# Sheet1.net
KiCad netlist of a schematic drawn in Altium Designer
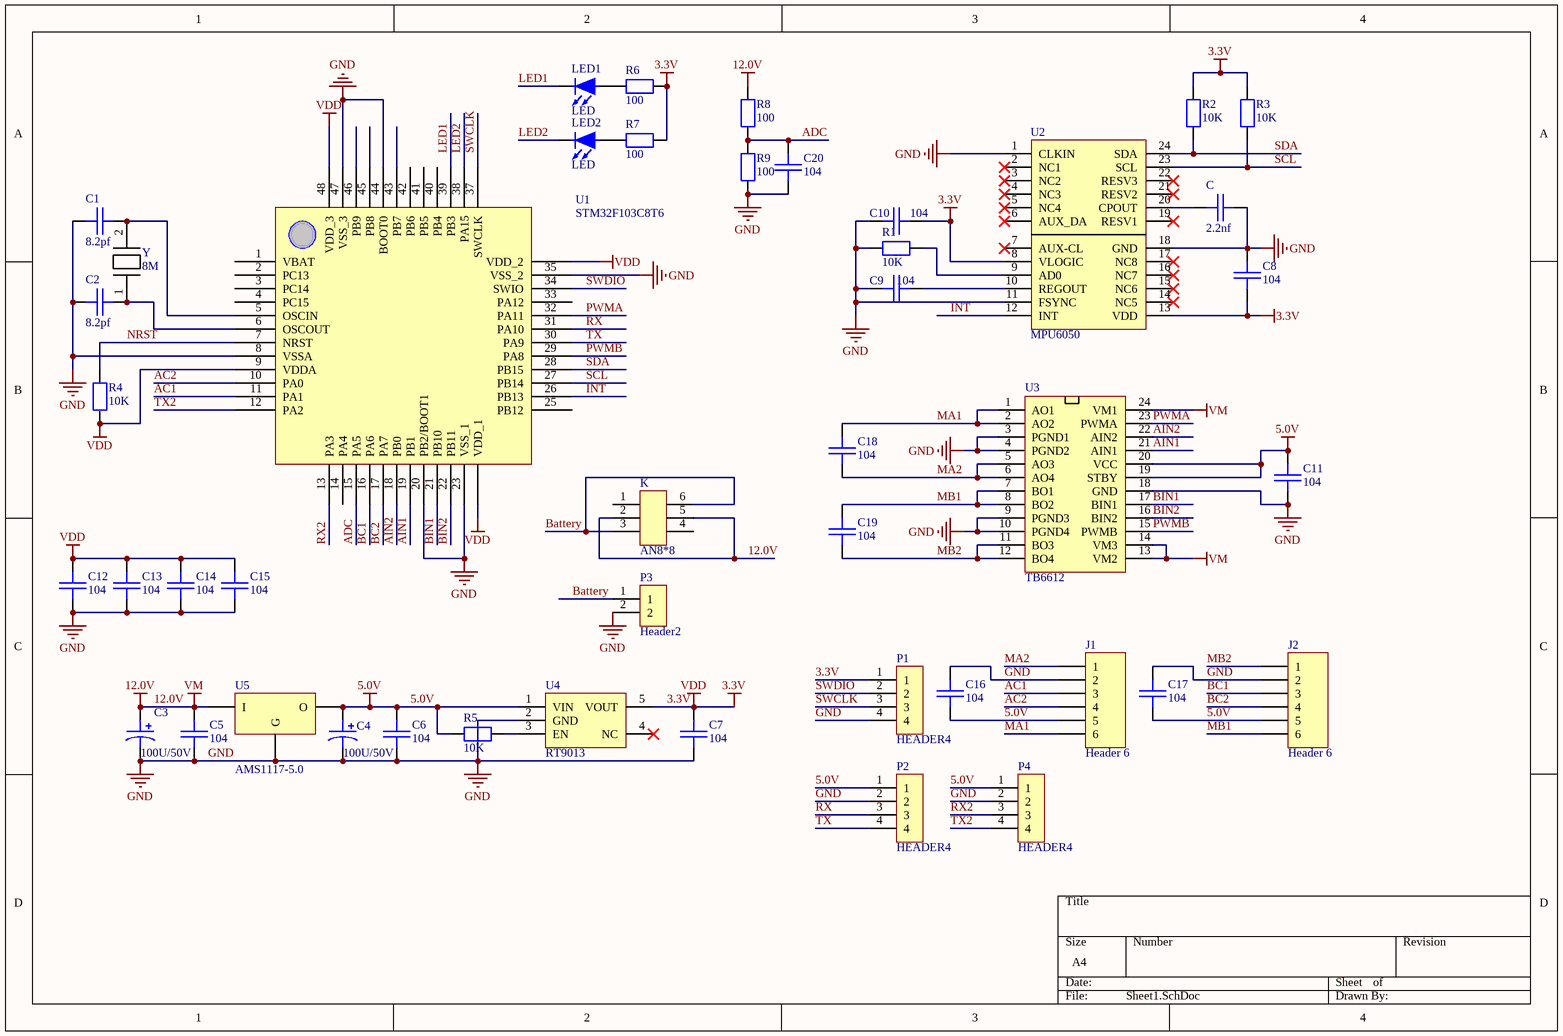
[diagram p0: Sheet1.SchDoc]

(export (version "E")
  (design (tool "Eeschema 10.0.6"))
  (components
    (comp (ref "C") (value "2.2nf") (footprint "0603") (libsource (lib "电容") (part "2.2nf")))
    (comp (ref "C1") (value "8.2pf") (footprint "0805-C") (libsource (lib "电容") (part "8.2pf")))
    (comp (ref "C2") (value "8.2pf") (footprint "0805-C") (libsource (lib "电容") (part "8.2pf")))
    (comp (ref "C3") (value "100U/50V") (footprint "RB_D8_d3.5") (libsource (lib "电容") (part "100U/50V")))
    (comp (ref "C4") (value "100U/50V") (footprint "RB_D8_d3.5") (libsource (lib "电容") (part "100U/50V")))
    (comp (ref "C5") (value "104") (footprint "0805-C") (libsource (lib "电容") (part "8.2pf")))
    (comp (ref "C6") (value "104") (footprint "0805-C") (libsource (lib "电容") (part "8.2pf")))
    (comp (ref "C7") (value "104") (footprint "0805-C") (libsource (lib "电容") (part "8.2pf")))
    (comp (ref "C8") (value "104") (footprint "0805-C") (libsource (lib "电容") (part "8.2pf")))
    (comp (ref "C9") (value "104") (footprint "0805-C") (libsource (lib "电容") (part "8.2pf")))
    (comp (ref "C10") (value "104") (footprint "0805-C") (libsource (lib "电容") (part "8.2pf")))
    (comp (ref "C11") (value "104") (footprint "0805-C") (libsource (lib "电容") (part "8.2pf")))
    (comp (ref "C12") (value "104") (footprint "0805-C") (libsource (lib "电容") (part "8.2pf")))
    (comp (ref "C13") (value "104") (footprint "0805-C") (libsource (lib "电容") (part "8.2pf")))
    (comp (ref "C14") (value "104") (footprint "0805-C") (libsource (lib "电容") (part "8.2pf")))
    (comp (ref "C15") (value "104") (footprint "0805-C") (libsource (lib "电容") (part "8.2pf")))
    (comp (ref "C16") (value "104") (footprint "0805-C") (libsource (lib "电容") (part "8.2pf")))
    (comp (ref "C17") (value "104") (footprint "0805-C") (libsource (lib "电容") (part "8.2pf")))
    (comp (ref "C18") (value "104") (footprint "0805-C") (libsource (lib "电容") (part "8.2pf")))
    (comp (ref "C19") (value "104") (footprint "0805-C") (libsource (lib "电容") (part "8.2pf")))
    (comp (ref "C20") (value "104") (footprint "0805-C") (libsource (lib "电容") (part "8.2pf")))
    (comp (ref "J1")
      (value "Header 6")
      (footprint "HDR1X6")
      (description "Header, 6-Pin")
      (fields (field (name "PUBLISHER") "Altium Limited"))
      (libsource (lib "接插件") (part "Header 6"))
    )
    (comp (ref "J2")
      (value "Header 6")
      (footprint "HDR1X6")
      (description "Header, 6-Pin")
      (fields (field (name "PUBLISHER") "Altium Limited"))
      (libsource (lib "接插件") (part "Header 6"))
    )
    (comp (ref "K") (value "AN8*8") (footprint "DIP-AN88") (libsource (lib "接插件") (part "AN8*8")))
    (comp (ref "LED1") (value "LED") (footprint "LED-0805") (libsource (lib "晶体管") (part "LED")))
    (comp (ref "LED2") (value "LED") (footprint "LED-0805") (libsource (lib "晶体管") (part "LED")))
    (comp (ref "P1") (value "HEADER4") (footprint "HDR1X4") (libsource (lib "接插件") (part "HEADER4")))
    (comp (ref "P2") (value "HEADER4") (footprint "HDR1X4") (libsource (lib "接插件") (part "HEADER4")))
    (comp (ref "P3") (value "Header2") (footprint "HDR1X2") (libsource (lib "接插件") (part "Header2")))
    (comp (ref "P4") (value "HEADER4") (footprint "HDR1X4") (libsource (lib "接插件") (part "HEADER4")))
    (comp (ref "R1") (value "10K") (footprint "0805-R") (libsource (lib "电阻") (part "10K-0805")))
    (comp (ref "R2") (value "10K") (footprint "0805-R") (libsource (lib "电阻") (part "10K-0805")))
    (comp (ref "R3") (value "10K") (footprint "0805-R") (libsource (lib "电阻") (part "10K-0805")))
    (comp (ref "R4") (value "10K") (footprint "0805-R") (libsource (lib "电阻") (part "10K-0805")))
    (comp (ref "R5") (value "10K") (footprint "0805-R") (libsource (lib "电阻") (part "10K-0805")))
    (comp (ref "R6") (value "100") (footprint "0805-R") (libsource (lib "电阻") (part "10K-0805")))
    (comp (ref "R7") (value "100") (footprint "0805-R") (libsource (lib "电阻") (part "10K-0805")))
    (comp (ref "R8") (value "100") (footprint "0805-R") (libsource (lib "电阻") (part "10K-0805")))
    (comp (ref "R9") (value "100") (footprint "0805-R") (libsource (lib "电阻") (part "10K-0805")))
    (comp (ref "U1")
      (value "STM32F103C8T6")
      (footprint "LQFP-48")
      (libsource (lib "IC") (part "STM32F103C8T6"))
    )
    (comp (ref "U2") (value "MPU6050") (footprint "QFN-24") (libsource (lib "IC") (part "MPU6050")))
    (comp (ref "U3") (value "TB6612") (footprint "SSOP-24") (libsource (lib "IC") (part "TB6612")))
    (comp (ref "U4") (value "RT9013") (footprint "SOT-23-5") (libsource (lib "IC") (part "RT9013")))
    (comp (ref "U5") (value "AMS1117-5.0") (footprint "SOT-223") (libsource (lib "IC") (part "AMS1117-5.0")))
    (comp (ref "Y") (value "8M") (footprint "HC-49SMD") (libsource (lib "接插件") (part "晶振 8M")))
  )
  (nets
    (net (code "1") (name "/AC1") (class "Default")
      (node (ref "J1") (pin "3") (pinfunction "3_3") (pintype "passive"))
      (node (ref "U1") (pin "11") (pinfunction "PA1_11") (pintype "passive"))
    )
    (net (code "2") (name "/AC2") (class "Default")
      (node (ref "J1") (pin "4") (pinfunction "4_4") (pintype "passive"))
      (node (ref "U1") (pin "10") (pinfunction "PA0_10") (pintype "passive"))
    )
    (net (code "3") (name "/ADC") (class "Default")
      (node (ref "C20") (pin "1") (pinfunction "1_1") (pintype "passive"))
      (node (ref "R8") (pin "1") (pinfunction "1_1") (pintype "passive"))
      (node (ref "R9") (pin "2") (pinfunction "2_2") (pintype "passive"))
      (node (ref "U1") (pin "15") (pinfunction "PA5_15") (pintype "passive"))
    )
    (net (code "4") (name "/AIN1") (class "Default")
      (node (ref "U1") (pin "19") (pinfunction "PB1_19") (pintype "passive"))
      (node (ref "U3") (pin "21") (pinfunction "AIN1_21") (pintype "passive"))
    )
    (net (code "5") (name "/AIN2") (class "Default")
      (node (ref "U1") (pin "18") (pinfunction "PB0_18") (pintype "passive"))
      (node (ref "U3") (pin "22") (pinfunction "AIN2_22") (pintype "passive"))
    )
    (net (code "6") (name "/BC1") (class "Default")
      (node (ref "J2") (pin "3") (pinfunction "3_3") (pintype "passive"))
      (node (ref "U1") (pin "16") (pinfunction "PA6_16") (pintype "passive"))
    )
    (net (code "7") (name "/BC2") (class "Default")
      (node (ref "J2") (pin "4") (pinfunction "4_4") (pintype "passive"))
      (node (ref "U1") (pin "17") (pinfunction "PA7_17") (pintype "passive"))
    )
    (net (code "8") (name "/BIN1") (class "Default")
      (node (ref "U1") (pin "21") (pinfunction "PB10_21") (pintype "passive"))
      (node (ref "U3") (pin "17") (pinfunction "BIN1_17") (pintype "passive"))
    )
    (net (code "9") (name "/BIN2") (class "Default")
      (node (ref "U1") (pin "22") (pinfunction "PB11_22") (pintype "passive"))
      (node (ref "U3") (pin "16") (pinfunction "BIN2_16") (pintype "passive"))
    )
    (net (code "10") (name "/Battery") (class "Default")
      (node (ref "K") (pin "3") (pinfunction "3_3") (pintype "passive"))
      (node (ref "K") (pin "6") (pinfunction "6_6") (pintype "passive"))
      (node (ref "P3") (pin "1") (pinfunction "1_1") (pintype "passive"))
    )
    (net (code "11") (name "/INT") (class "Default")
      (node (ref "U1") (pin "26") (pinfunction "PB13_26") (pintype "passive"))
      (node (ref "U2") (pin "12") (pinfunction "INT_12") (pintype "passive"))
    )
    (net (code "12") (name "/LED1") (class "Default")
      (node (ref "LED1") (pin "2") (pinfunction "2_2") (pintype "passive"))
      (node (ref "U1") (pin "39") (pinfunction "PB3_39") (pintype "passive"))
    )
    (net (code "13") (name "/LED2") (class "Default")
      (node (ref "LED2") (pin "2") (pinfunction "2_2") (pintype "passive"))
      (node (ref "U1") (pin "38") (pinfunction "PA15_38") (pintype "passive"))
    )
    (net (code "14") (name "/MA1") (class "Default")
      (node (ref "C18") (pin "1") (pinfunction "1_1") (pintype "passive"))
      (node (ref "J1") (pin "6") (pinfunction "6_6") (pintype "passive"))
      (node (ref "U3") (pin "1") (pinfunction "AO1_1") (pintype "passive"))
      (node (ref "U3") (pin "2") (pinfunction "AO2_2") (pintype "passive"))
    )
    (net (code "15") (name "/MA2") (class "Default")
      (node (ref "C18") (pin "2") (pinfunction "2_2") (pintype "passive"))
      (node (ref "J1") (pin "1") (pinfunction "1_1") (pintype "passive"))
      (node (ref "U3") (pin "5") (pinfunction "AO3_5") (pintype "passive"))
      (node (ref "U3") (pin "6") (pinfunction "AO4_6") (pintype "passive"))
    )
    (net (code "16") (name "/MB1") (class "Default")
      (node (ref "C19") (pin "1") (pinfunction "1_1") (pintype "passive"))
      (node (ref "J2") (pin "6") (pinfunction "6_6") (pintype "passive"))
      (node (ref "U3") (pin "7") (pinfunction "BO1_7") (pintype "passive"))
      (node (ref "U3") (pin "8") (pinfunction "BO2_8") (pintype "passive"))
    )
    (net (code "17") (name "/MB2") (class "Default")
      (node (ref "C19") (pin "2") (pinfunction "2_2") (pintype "passive"))
      (node (ref "J2") (pin "1") (pinfunction "1_1") (pintype "passive"))
      (node (ref "U3") (pin "11") (pinfunction "BO3_11") (pintype "passive"))
      (node (ref "U3") (pin "12") (pinfunction "BO4_12") (pintype "passive"))
    )
    (net (code "18") (name "/NRST") (class "Default")
      (node (ref "R4") (pin "2") (pinfunction "2_2") (pintype "passive"))
      (node (ref "U1") (pin "7") (pinfunction "NRST_7") (pintype "passive"))
    )
    (net (code "19") (name "/PWMA") (class "Default")
      (node (ref "U1") (pin "32") (pinfunction "PA11_32") (pintype "passive"))
      (node (ref "U3") (pin "23") (pinfunction "PWMA_23") (pintype "passive"))
    )
    (net (code "20") (name "/PWMB") (class "Default")
      (node (ref "U1") (pin "29") (pinfunction "PA8_29") (pintype "passive"))
      (node (ref "U3") (pin "15") (pinfunction "PWMB_15") (pintype "passive"))
    )
    (net (code "21") (name "/RX") (class "Default")
      (node (ref "P2") (pin "3") (pinfunction "3_3") (pintype "passive"))
      (node (ref "U1") (pin "31") (pinfunction "PA10_31") (pintype "passive"))
    )
    (net (code "22") (name "/RX2") (class "Default")
      (node (ref "P4") (pin "3") (pinfunction "3_3") (pintype "passive"))
      (node (ref "U1") (pin "13") (pinfunction "PA3_13") (pintype "passive"))
    )
    (net (code "23") (name "/SCL") (class "Default")
      (node (ref "R3") (pin "1") (pinfunction "1_1") (pintype "passive"))
      (node (ref "U1") (pin "27") (pinfunction "PB14_27") (pintype "passive"))
      (node (ref "U2") (pin "23") (pinfunction "SCL_23") (pintype "passive"))
    )
    (net (code "24") (name "/SDA") (class "Default")
      (node (ref "R2") (pin "1") (pinfunction "1_1") (pintype "passive"))
      (node (ref "U1") (pin "28") (pinfunction "PB15_28") (pintype "passive"))
      (node (ref "U2") (pin "24") (pinfunction "SDA_24") (pintype "passive"))
    )
    (net (code "25") (name "/SWCLK") (class "Default")
      (node (ref "P1") (pin "3") (pinfunction "3_3") (pintype "passive"))
      (node (ref "U1") (pin "37") (pinfunction "SWCLK_37") (pintype "passive"))
    )
    (net (code "26") (name "/SWDIO") (class "Default")
      (node (ref "P1") (pin "2") (pinfunction "2_2") (pintype "passive"))
      (node (ref "U1") (pin "34") (pinfunction "SWIO_34") (pintype "passive"))
    )
    (net (code "27") (name "/TX") (class "Default")
      (node (ref "P2") (pin "4") (pinfunction "4_4") (pintype "passive"))
      (node (ref "U1") (pin "30") (pinfunction "PA9_30") (pintype "passive"))
    )
    (net (code "28") (name "/TX2") (class "Default")
      (node (ref "P4") (pin "4") (pinfunction "4_4") (pintype "passive"))
      (node (ref "U1") (pin "12") (pinfunction "PA2_12") (pintype "passive"))
    )
    (net (code "29") (name "3.3V") (class "Default")
      (node (ref "C10") (pin "1") (pinfunction "1_1") (pintype "passive"))
      (node (ref "C12") (pin "1") (pinfunction "1_1") (pintype "passive"))
      (node (ref "C13") (pin "1") (pinfunction "1_1") (pintype "passive"))
      (node (ref "C14") (pin "1") (pinfunction "1_1") (pintype "passive"))
      (node (ref "C15") (pin "1") (pinfunction "1_1") (pintype "passive"))
      (node (ref "C7") (pin "1") (pinfunction "1_1") (pintype "passive"))
      (node (ref "C8") (pin "1") (pinfunction "1_1") (pintype "passive"))
      (node (ref "P1") (pin "1") (pinfunction "1_1") (pintype "passive"))
      (node (ref "R2") (pin "2") (pinfunction "2_2") (pintype "passive"))
      (node (ref "R3") (pin "2") (pinfunction "2_2") (pintype "passive"))
      (node (ref "R4") (pin "1") (pinfunction "1_1") (pintype "passive"))
      (node (ref "R6") (pin "2") (pinfunction "2_2") (pintype "passive"))
      (node (ref "R7") (pin "2") (pinfunction "2_2") (pintype "passive"))
      (node (ref "U1") (pin "24") (pinfunction "VDD_1_24") (pintype "passive"))
      (node (ref "U1") (pin "36") (pinfunction "VDD_2_36") (pintype "passive"))
      (node (ref "U1") (pin "48") (pinfunction "VDD_3_48") (pintype "passive"))
      (node (ref "U1") (pin "9") (pinfunction "VDDA_9") (pintype "passive"))
      (node (ref "U2") (pin "13") (pinfunction "VDD_13") (pintype "passive"))
      (node (ref "U2") (pin "8") (pinfunction "VLOGIC_8") (pintype "passive"))
      (node (ref "U4") (pin "5") (pinfunction "VOUT_5") (pintype "passive"))
    )
    (net (code "30") (name "5.0V") (class "Default")
      (node (ref "C11") (pin "1") (pinfunction "1_1") (pintype "passive"))
      (node (ref "C16") (pin "2") (pinfunction "2_2") (pintype "passive"))
      (node (ref "C17") (pin "2") (pinfunction "2_2") (pintype "passive"))
      (node (ref "C4") (pin "1") (pinfunction "1_1") (pintype "passive"))
      (node (ref "C6") (pin "1") (pinfunction "1_1") (pintype "passive"))
      (node (ref "J1") (pin "5") (pinfunction "5_5") (pintype "passive"))
      (node (ref "J2") (pin "5") (pinfunction "5_5") (pintype "passive"))
      (node (ref "P2") (pin "1") (pinfunction "1_1") (pintype "passive"))
      (node (ref "P4") (pin "1") (pinfunction "1_1") (pintype "passive"))
      (node (ref "R5") (pin "2") (pinfunction "2_2") (pintype "passive"))
      (node (ref "U3") (pin "19") (pinfunction "STBY_19") (pintype "passive"))
      (node (ref "U3") (pin "20") (pinfunction "VCC_20") (pintype "passive"))
      (node (ref "U4") (pin "1") (pinfunction "VIN_1") (pintype "passive"))
      (node (ref "U5") (pin "2") (pinfunction "O_2") (pintype "passive"))
    )
    (net (code "31") (name "12.0V") (class "Default")
      (node (ref "C3") (pin "1") (pinfunction "1_1") (pintype "passive"))
      (node (ref "C5") (pin "1") (pinfunction "1_1") (pintype "passive"))
      (node (ref "K") (pin "2") (pinfunction "2_2") (pintype "passive"))
      (node (ref "K") (pin "5") (pinfunction "5_5") (pintype "passive"))
      (node (ref "R8") (pin "2") (pinfunction "2_2") (pintype "passive"))
      (node (ref "U3") (pin "13") (pinfunction "VM2_13") (pintype "passive"))
      (node (ref "U3") (pin "14") (pinfunction "VM3_14") (pintype "passive"))
      (node (ref "U3") (pin "24") (pinfunction "VM1_24") (pintype "passive"))
      (node (ref "U5") (pin "3") (pinfunction "I_3") (pintype "passive"))
    )
    (net (code "32") (name "GND") (class "Default")
      (node (ref "C") (pin "2") (pinfunction "2_2") (pintype "passive"))
      (node (ref "C1") (pin "2") (pinfunction "2_2") (pintype "passive"))
      (node (ref "C10") (pin "2") (pinfunction "2_2") (pintype "passive"))
      (node (ref "C11") (pin "2") (pinfunction "2_2") (pintype "passive"))
      (node (ref "C12") (pin "2") (pinfunction "2_2") (pintype "passive"))
      (node (ref "C13") (pin "2") (pinfunction "2_2") (pintype "passive"))
      (node (ref "C14") (pin "2") (pinfunction "2_2") (pintype "passive"))
      (node (ref "C15") (pin "2") (pinfunction "2_2") (pintype "passive"))
      (node (ref "C16") (pin "1") (pinfunction "1_1") (pintype "passive"))
      (node (ref "C17") (pin "1") (pinfunction "1_1") (pintype "passive"))
      (node (ref "C2") (pin "2") (pinfunction "2_2") (pintype "passive"))
      (node (ref "C20") (pin "2") (pinfunction "2_2") (pintype "passive"))
      (node (ref "C3") (pin "2") (pinfunction "2_2") (pintype "passive"))
      (node (ref "C4") (pin "2") (pinfunction "2_2") (pintype "passive"))
      (node (ref "C5") (pin "2") (pinfunction "2_2") (pintype "passive"))
      (node (ref "C6") (pin "2") (pinfunction "2_2") (pintype "passive"))
      (node (ref "C7") (pin "2") (pinfunction "2_2") (pintype "passive"))
      (node (ref "C8") (pin "2") (pinfunction "2_2") (pintype "passive"))
      (node (ref "C9") (pin "2") (pinfunction "2_2") (pintype "passive"))
      (node (ref "J1") (pin "2") (pinfunction "2_2") (pintype "passive"))
      (node (ref "J2") (pin "2") (pinfunction "2_2") (pintype "passive"))
      (node (ref "P1") (pin "4") (pinfunction "4_4") (pintype "passive"))
      (node (ref "P2") (pin "2") (pinfunction "2_2") (pintype "passive"))
      (node (ref "P3") (pin "2") (pinfunction "2_2") (pintype "passive"))
      (node (ref "P4") (pin "2") (pinfunction "2_2") (pintype "passive"))
      (node (ref "R1") (pin "1") (pinfunction "1_1") (pintype "passive"))
      (node (ref "R9") (pin "1") (pinfunction "1_1") (pintype "passive"))
      (node (ref "U1") (pin "20") (pinfunction "PB2/BOOT1_20") (pintype "passive"))
      (node (ref "U1") (pin "23") (pinfunction "VSS_1_23") (pintype "passive"))
      (node (ref "U1") (pin "35") (pinfunction "VSS_2_35") (pintype "passive"))
      (node (ref "U1") (pin "44") (pinfunction "BOOT0_44") (pintype "passive"))
      (node (ref "U1") (pin "47") (pinfunction "VSS_3_47") (pintype "passive"))
      (node (ref "U1") (pin "8") (pinfunction "VSSA_8") (pintype "passive"))
      (node (ref "U2") (pin "1") (pinfunction "CLKIN_1") (pintype "passive"))
      (node (ref "U2") (pin "11") (pinfunction "FSYNC_11") (pintype "passive"))
      (node (ref "U2") (pin "18") (pinfunction "GND_18") (pintype "passive"))
      (node (ref "U3") (pin "10") (pinfunction "PGND4_10") (pintype "passive"))
      (node (ref "U3") (pin "18") (pinfunction "GND_18") (pintype "passive"))
      (node (ref "U3") (pin "3") (pinfunction "PGND1_3") (pintype "passive"))
      (node (ref "U3") (pin "4") (pinfunction "PGND2_4") (pintype "passive"))
      (node (ref "U3") (pin "9") (pinfunction "PGND3_9") (pintype "passive"))
      (node (ref "U4") (pin "2") (pinfunction "GND_2") (pintype "passive"))
      (node (ref "U5") (pin "1") (pinfunction "G_1") (pintype "passive"))
    )
    (net (code "33") (name "Net-(LED1-Pad1)") (class "Default")
      (node (ref "LED1") (pin "1") (pinfunction "1_1") (pintype "passive"))
      (node (ref "R6") (pin "1") (pinfunction "1_1") (pintype "passive"))
    )
    (net (code "34") (name "Net-(LED2-Pad1)") (class "Default")
      (node (ref "LED2") (pin "1") (pinfunction "1_1") (pintype "passive"))
      (node (ref "R7") (pin "1") (pinfunction "1_1") (pintype "passive"))
    )
    (net (code "35") (name "Net-(U1-OSCIN)") (class "Default")
      (node (ref "C1") (pin "1") (pinfunction "1_1") (pintype "passive"))
      (node (ref "U1") (pin "5") (pinfunction "OSCIN_5") (pintype "passive"))
      (node (ref "Y") (pin "2") (pinfunction "2_2") (pintype "passive"))
    )
    (net (code "36") (name "Net-(U1-OSCOUT)") (class "Default")
      (node (ref "C2") (pin "1") (pinfunction "1_1") (pintype "passive"))
      (node (ref "U1") (pin "6") (pinfunction "OSCOUT_6") (pintype "passive"))
      (node (ref "Y") (pin "1") (pinfunction "1_1") (pintype "passive"))
    )
    (net (code "37") (name "Net-(U2-AD0)") (class "Default")
      (node (ref "R1") (pin "2") (pinfunction "2_2") (pintype "passive"))
      (node (ref "U2") (pin "9") (pinfunction "AD0_9") (pintype "passive"))
    )
    (net (code "38") (name "Net-(U2-CPOUT)") (class "Default")
      (node (ref "C") (pin "1") (pinfunction "1_1") (pintype "passive"))
      (node (ref "U2") (pin "20") (pinfunction "CPOUT_20") (pintype "passive"))
    )
    (net (code "39") (name "Net-(U2-REGOUT)") (class "Default")
      (node (ref "C9") (pin "1") (pinfunction "1_1") (pintype "passive"))
      (node (ref "U2") (pin "10") (pinfunction "REGOUT_10") (pintype "passive"))
    )
    (net (code "40") (name "Net-(U4-EN)") (class "Default")
      (node (ref "R5") (pin "1") (pinfunction "1_1") (pintype "passive"))
      (node (ref "U4") (pin "3") (pinfunction "EN_3") (pintype "passive"))
    )
    (net (code "41") (name "unconnected-(K-Pad1)") (class "Default")
      (node (ref "K") (pin "1") (pinfunction "1_1") (pintype "passive"))
    )
    (net (code "42") (name "unconnected-(K-Pad4)") (class "Default")
      (node (ref "K") (pin "4") (pinfunction "4_4") (pintype "passive"))
    )
    (net (code "43") (name "unconnected-(U1-PA4-Pad14)") (class "Default")
      (node (ref "U1") (pin "14") (pinfunction "PA4_14") (pintype "passive"))
    )
    (net (code "44") (name "unconnected-(U1-PA12-Pad33)") (class "Default")
      (node (ref "U1") (pin "33") (pinfunction "PA12_33") (pintype "passive"))
    )
    (net (code "45") (name "unconnected-(U1-PB4-Pad40)") (class "Default")
      (node (ref "U1") (pin "40") (pinfunction "PB4_40") (pintype "passive"))
    )
    (net (code "46") (name "unconnected-(U1-PB5-Pad41)") (class "Default")
      (node (ref "U1") (pin "41") (pinfunction "PB5_41") (pintype "passive"))
    )
    (net (code "47") (name "unconnected-(U1-PB6-Pad42)") (class "Default")
      (node (ref "U1") (pin "42") (pinfunction "PB6_42") (pintype "passive"))
    )
    (net (code "48") (name "unconnected-(U1-PB7-Pad43)") (class "Default")
      (node (ref "U1") (pin "43") (pinfunction "PB7_43") (pintype "passive"))
    )
    (net (code "49") (name "unconnected-(U1-PB8-Pad45)") (class "Default")
      (node (ref "U1") (pin "45") (pinfunction "PB8_45") (pintype "passive"))
    )
    (net (code "50") (name "unconnected-(U1-PB9-Pad46)") (class "Default")
      (node (ref "U1") (pin "46") (pinfunction "PB9_46") (pintype "passive"))
    )
    (net (code "51") (name "unconnected-(U1-PB12-Pad25)") (class "Default")
      (node (ref "U1") (pin "25") (pinfunction "PB12_25") (pintype "passive"))
    )
    (net (code "52") (name "unconnected-(U1-PC13-Pad2)") (class "Default")
      (node (ref "U1") (pin "2") (pinfunction "PC13_2") (pintype "passive"))
    )
    (net (code "53") (name "unconnected-(U1-PC14-Pad3)") (class "Default")
      (node (ref "U1") (pin "3") (pinfunction "PC14_3") (pintype "passive"))
    )
    (net (code "54") (name "unconnected-(U1-PC15-Pad4)") (class "Default")
      (node (ref "U1") (pin "4") (pinfunction "PC15_4") (pintype "passive"))
    )
    (net (code "55") (name "unconnected-(U1-VBAT-Pad1)") (class "Default")
      (node (ref "U1") (pin "1") (pinfunction "VBAT_1") (pintype "passive"))
    )
    (net (code "56") (name "unconnected-(U2-AUX-CL-Pad7)") (class "Default")
      (node (ref "U2") (pin "7") (pinfunction "AUX-CL_7") (pintype "passive+no_connect"))
    )
    (net (code "57") (name "unconnected-(U2-AUX_DA-Pad6)") (class "Default")
      (node (ref "U2") (pin "6") (pinfunction "AUX_DA_6") (pintype "passive+no_connect"))
    )
    (net (code "58") (name "unconnected-(U2-NC1-Pad2)") (class "Default")
      (node (ref "U2") (pin "2") (pinfunction "NC1_2") (pintype "passive+no_connect"))
    )
    (net (code "59") (name "unconnected-(U2-NC2-Pad3)") (class "Default")
      (node (ref "U2") (pin "3") (pinfunction "NC2_3") (pintype "passive+no_connect"))
    )
    (net (code "60") (name "unconnected-(U2-NC3-Pad4)") (class "Default")
      (node (ref "U2") (pin "4") (pinfunction "NC3_4") (pintype "passive+no_connect"))
    )
    (net (code "61") (name "unconnected-(U2-NC4-Pad5)") (class "Default")
      (node (ref "U2") (pin "5") (pinfunction "NC4_5") (pintype "passive+no_connect"))
    )
    (net (code "62") (name "unconnected-(U2-NC5-Pad14)") (class "Default")
      (node (ref "U2") (pin "14") (pinfunction "NC5_14") (pintype "passive+no_connect"))
    )
    (net (code "63") (name "unconnected-(U2-NC6-Pad15)") (class "Default")
      (node (ref "U2") (pin "15") (pinfunction "NC6_15") (pintype "passive+no_connect"))
    )
    (net (code "64") (name "unconnected-(U2-NC7-Pad16)") (class "Default")
      (node (ref "U2") (pin "16") (pinfunction "NC7_16") (pintype "passive+no_connect"))
    )
    (net (code "65") (name "unconnected-(U2-NC8-Pad17)") (class "Default")
      (node (ref "U2") (pin "17") (pinfunction "NC8_17") (pintype "passive+no_connect"))
    )
    (net (code "66") (name "unconnected-(U2-RESV1-Pad19)") (class "Default")
      (node (ref "U2") (pin "19") (pinfunction "RESV1_19") (pintype "passive+no_connect"))
    )
    (net (code "67") (name "unconnected-(U2-RESV2-Pad21)") (class "Default")
      (node (ref "U2") (pin "21") (pinfunction "RESV2_21") (pintype "passive+no_connect"))
    )
    (net (code "68") (name "unconnected-(U2-RESV3-Pad22)") (class "Default")
      (node (ref "U2") (pin "22") (pinfunction "RESV3_22") (pintype "passive+no_connect"))
    )
    (net (code "69") (name "unconnected-(U4-NC-Pad4)") (class "Default")
      (node (ref "U4") (pin "4") (pinfunction "NC_4") (pintype "passive+no_connect"))
    )
  )
)
